# LegoConnectorX2.net
KiCad netlist of a schematic drawn in EAGLE
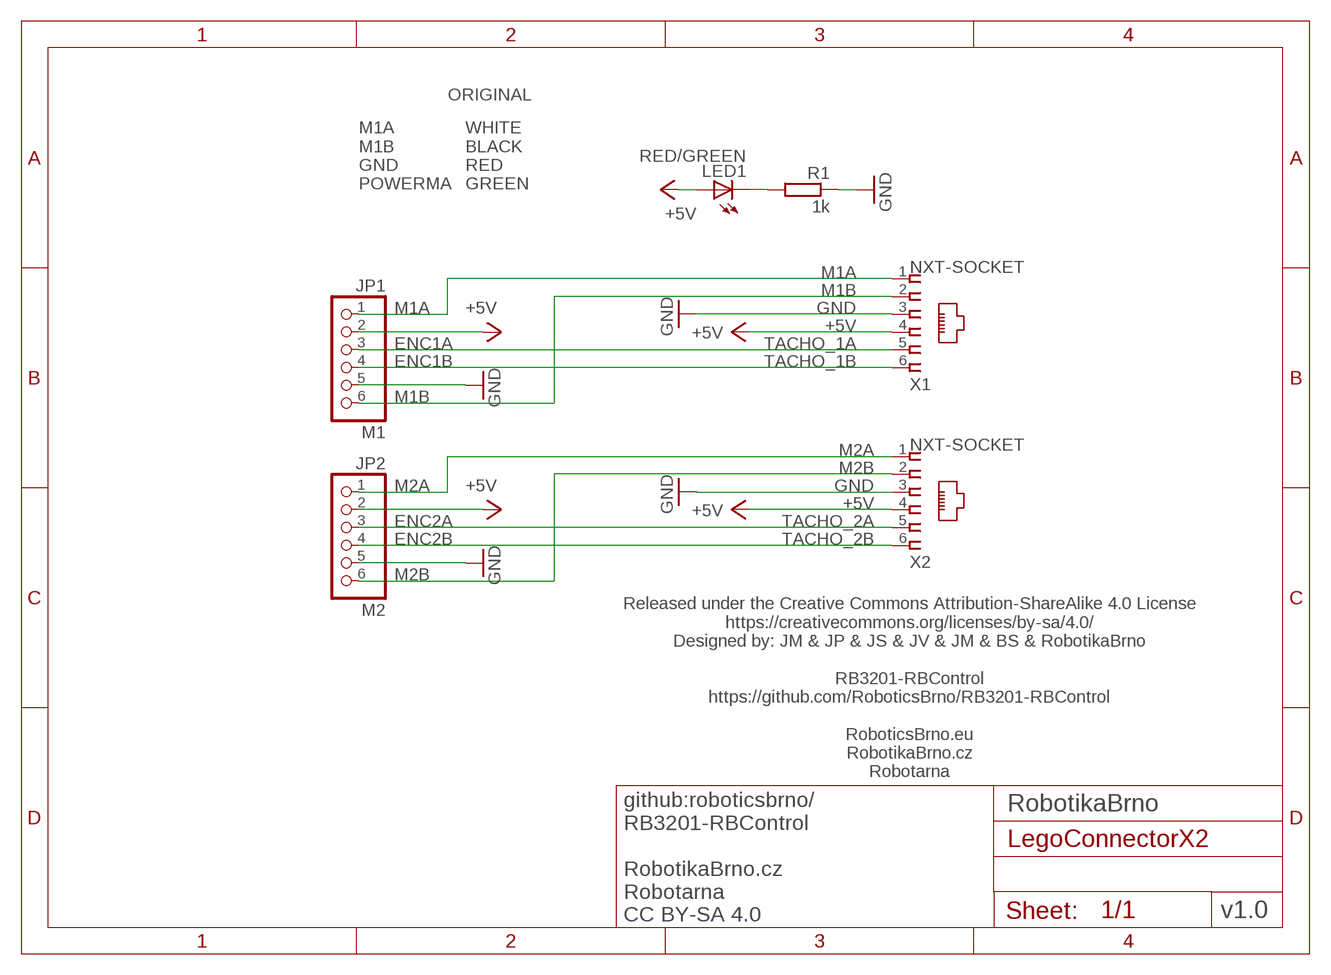
[diagram p0: schematic, sheet 1]

(export (version "E")
  (design (tool "Eeschema 10.0.6"))
  (components
    (comp (ref "JP1")
      (value "M1")
      (footprint "eagle-import:1X06")
      (libsource (lib "eagle-import") (part "PINHD-1X6"))
    )
    (comp (ref "JP2")
      (value "M2")
      (footprint "eagle-import:1X06")
      (libsource (lib "eagle-import") (part "PINHD-1X6"))
    )
    (comp (ref "LED1")
      (value "RED/GREEN")
      (footprint "eagle-import:SML0603")
      (libsource (lib "eagle-import") (part "LEDSML0603"))
    )
    (comp (ref "R1")
      (value "1k")
      (footprint "eagle-import:R0603")
      (libsource (lib "eagle-import") (part "R-EU_R0603"))
    )
    (comp (ref "X1")
      (value "NXT-SOCKET")
      (footprint "eagle-import:NXT-SOCKET")
      (libsource (lib "eagle-import") (part "NXT-SOCKET"))
    )
    (comp (ref "X2")
      (value "NXT-SOCKET")
      (footprint "eagle-import:NXT-SOCKET")
      (libsource (lib "eagle-import") (part "NXT-SOCKET"))
    )
  )
  (nets
    (net (code "1") (name "+5V") (class "Default")
      (node (ref "JP1") (pin "2") (pinfunction "2_2") (pintype "passive"))
      (node (ref "JP2") (pin "2") (pinfunction "2_2") (pintype "passive"))
      (node (ref "LED1") (pin "A") (pinfunction "A_A") (pintype "passive"))
      (node (ref "X1") (pin "4") (pinfunction "4_4") (pintype "passive"))
      (node (ref "X2") (pin "4") (pinfunction "4_4") (pintype "passive"))
    )
    (net (code "2") (name "/M1A") (class "Default")
      (node (ref "JP1") (pin "1") (pinfunction "1_1") (pintype "passive"))
      (node (ref "X1") (pin "1") (pinfunction "1_1") (pintype "passive"))
    )
    (net (code "3") (name "/M1B") (class "Default")
      (node (ref "JP1") (pin "6") (pinfunction "6_6") (pintype "passive"))
      (node (ref "X1") (pin "2") (pinfunction "2_2") (pintype "passive"))
    )
    (net (code "4") (name "/M2A") (class "Default")
      (node (ref "JP2") (pin "1") (pinfunction "1_1") (pintype "passive"))
      (node (ref "X2") (pin "1") (pinfunction "1_1") (pintype "passive"))
    )
    (net (code "5") (name "/M2B") (class "Default")
      (node (ref "JP2") (pin "6") (pinfunction "6_6") (pintype "passive"))
      (node (ref "X2") (pin "2") (pinfunction "2_2") (pintype "passive"))
    )
    (net (code "6") (name "/TACHO_1A") (class "Default")
      (node (ref "JP1") (pin "3") (pinfunction "3_3") (pintype "passive"))
      (node (ref "X1") (pin "5") (pinfunction "5_5") (pintype "passive"))
    )
    (net (code "7") (name "/TACHO_1B") (class "Default")
      (node (ref "JP1") (pin "4") (pinfunction "4_4") (pintype "passive"))
      (node (ref "X1") (pin "6") (pinfunction "6_6") (pintype "passive"))
    )
    (net (code "8") (name "/TACHO_2A") (class "Default")
      (node (ref "JP2") (pin "3") (pinfunction "3_3") (pintype "passive"))
      (node (ref "X2") (pin "5") (pinfunction "5_5") (pintype "passive"))
    )
    (net (code "9") (name "/TACHO_2B") (class "Default")
      (node (ref "JP2") (pin "4") (pinfunction "4_4") (pintype "passive"))
      (node (ref "X2") (pin "6") (pinfunction "6_6") (pintype "passive"))
    )
    (net (code "10") (name "GND") (class "Default")
      (node (ref "JP1") (pin "5") (pinfunction "5_5") (pintype "passive"))
      (node (ref "JP2") (pin "5") (pinfunction "5_5") (pintype "passive"))
      (node (ref "R1") (pin "1") (pinfunction "1_1") (pintype "passive"))
      (node (ref "X1") (pin "3") (pinfunction "3_3") (pintype "passive"))
      (node (ref "X2") (pin "3") (pinfunction "3_3") (pintype "passive"))
    )
    (net (code "11") (name "Net-(LED1-PadC)") (class "Default")
      (node (ref "LED1") (pin "C") (pinfunction "C_C") (pintype "passive"))
      (node (ref "R1") (pin "2") (pinfunction "2_2") (pintype "passive"))
    )
  )
)
